# CAN_Circuit.net
KiCad netlist of a schematic drawn in EAGLE
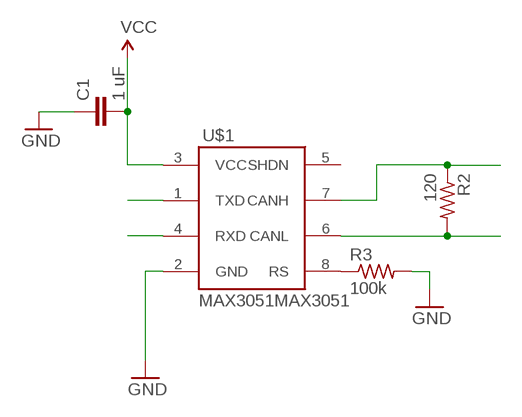
[diagram p0: schematic, sheet 1]

(export (version "E")
  (design (tool "Eeschema 10.0.6"))
  (components
    (comp (ref "C1")
      (value "1 uF")
      (footprint "eagle-import:C2.5-3")
      (libsource (lib "eagle-import") (part "C2,5-3"))
    )
    (comp (ref "R2")
      (value "120")
      (footprint "eagle-import:0204V")
      (libsource (lib "eagle-import") (part "R-US_0204/2V"))
    )
    (comp (ref "R3")
      (value "100k")
      (footprint "eagle-import:0204V")
      (libsource (lib "eagle-import") (part "R-US_0204/2V"))
    )
    (comp (ref "U$1")
      (value "MAX3051MAX3051")
      (footprint "eagle-import:SOT23-8L")
      (libsource (lib "eagle-import") (part "MAX3051MAX3051"))
    )
  )
  (nets
    (net (code "1") (name "GND") (class "Default")
      (node (ref "C1") (pin "1") (pinfunction "1_1") (pintype "passive"))
      (node (ref "R3") (pin "2") (pinfunction "2_2") (pintype "passive"))
      (node (ref "U$1") (pin "2") (pinfunction "GND_2") (pintype "bidirectional"))
    )
    (net (code "2") (name "Net-(U$1-CANH)") (class "Default")
      (node (ref "R2") (pin "1") (pinfunction "1_1") (pintype "passive"))
      (node (ref "U$1") (pin "7") (pinfunction "CANH_7") (pintype "bidirectional"))
    )
    (net (code "3") (name "Net-(U$1-CANL)") (class "Default")
      (node (ref "R2") (pin "2") (pinfunction "2_2") (pintype "passive"))
      (node (ref "U$1") (pin "6") (pinfunction "CANL_6") (pintype "bidirectional"))
    )
    (net (code "4") (name "Net-(U$1-RS)") (class "Default")
      (node (ref "R3") (pin "1") (pinfunction "1_1") (pintype "passive"))
      (node (ref "U$1") (pin "8") (pinfunction "RS_8") (pintype "bidirectional"))
    )
    (net (code "5") (name "VCC") (class "Default")
      (node (ref "C1") (pin "2") (pinfunction "2_2") (pintype "passive"))
      (node (ref "U$1") (pin "3") (pinfunction "VCC_3") (pintype "bidirectional"))
    )
    (net (code "6") (name "unconnected-(U$1-RXD-Pad4)") (class "Default")
      (node (ref "U$1") (pin "4") (pinfunction "RXD_4") (pintype "bidirectional"))
    )
    (net (code "7") (name "unconnected-(U$1-SHDN-Pad5)") (class "Default")
      (node (ref "U$1") (pin "5") (pinfunction "SHDN_5") (pintype "bidirectional"))
    )
    (net (code "8") (name "unconnected-(U$1-TXD-Pad1)") (class "Default")
      (node (ref "U$1") (pin "1") (pinfunction "TXD_1") (pintype "bidirectional"))
    )
  )
)
